# SCH_Macropad.net
KiCad netlist of a schematic drawn in EasyEDA
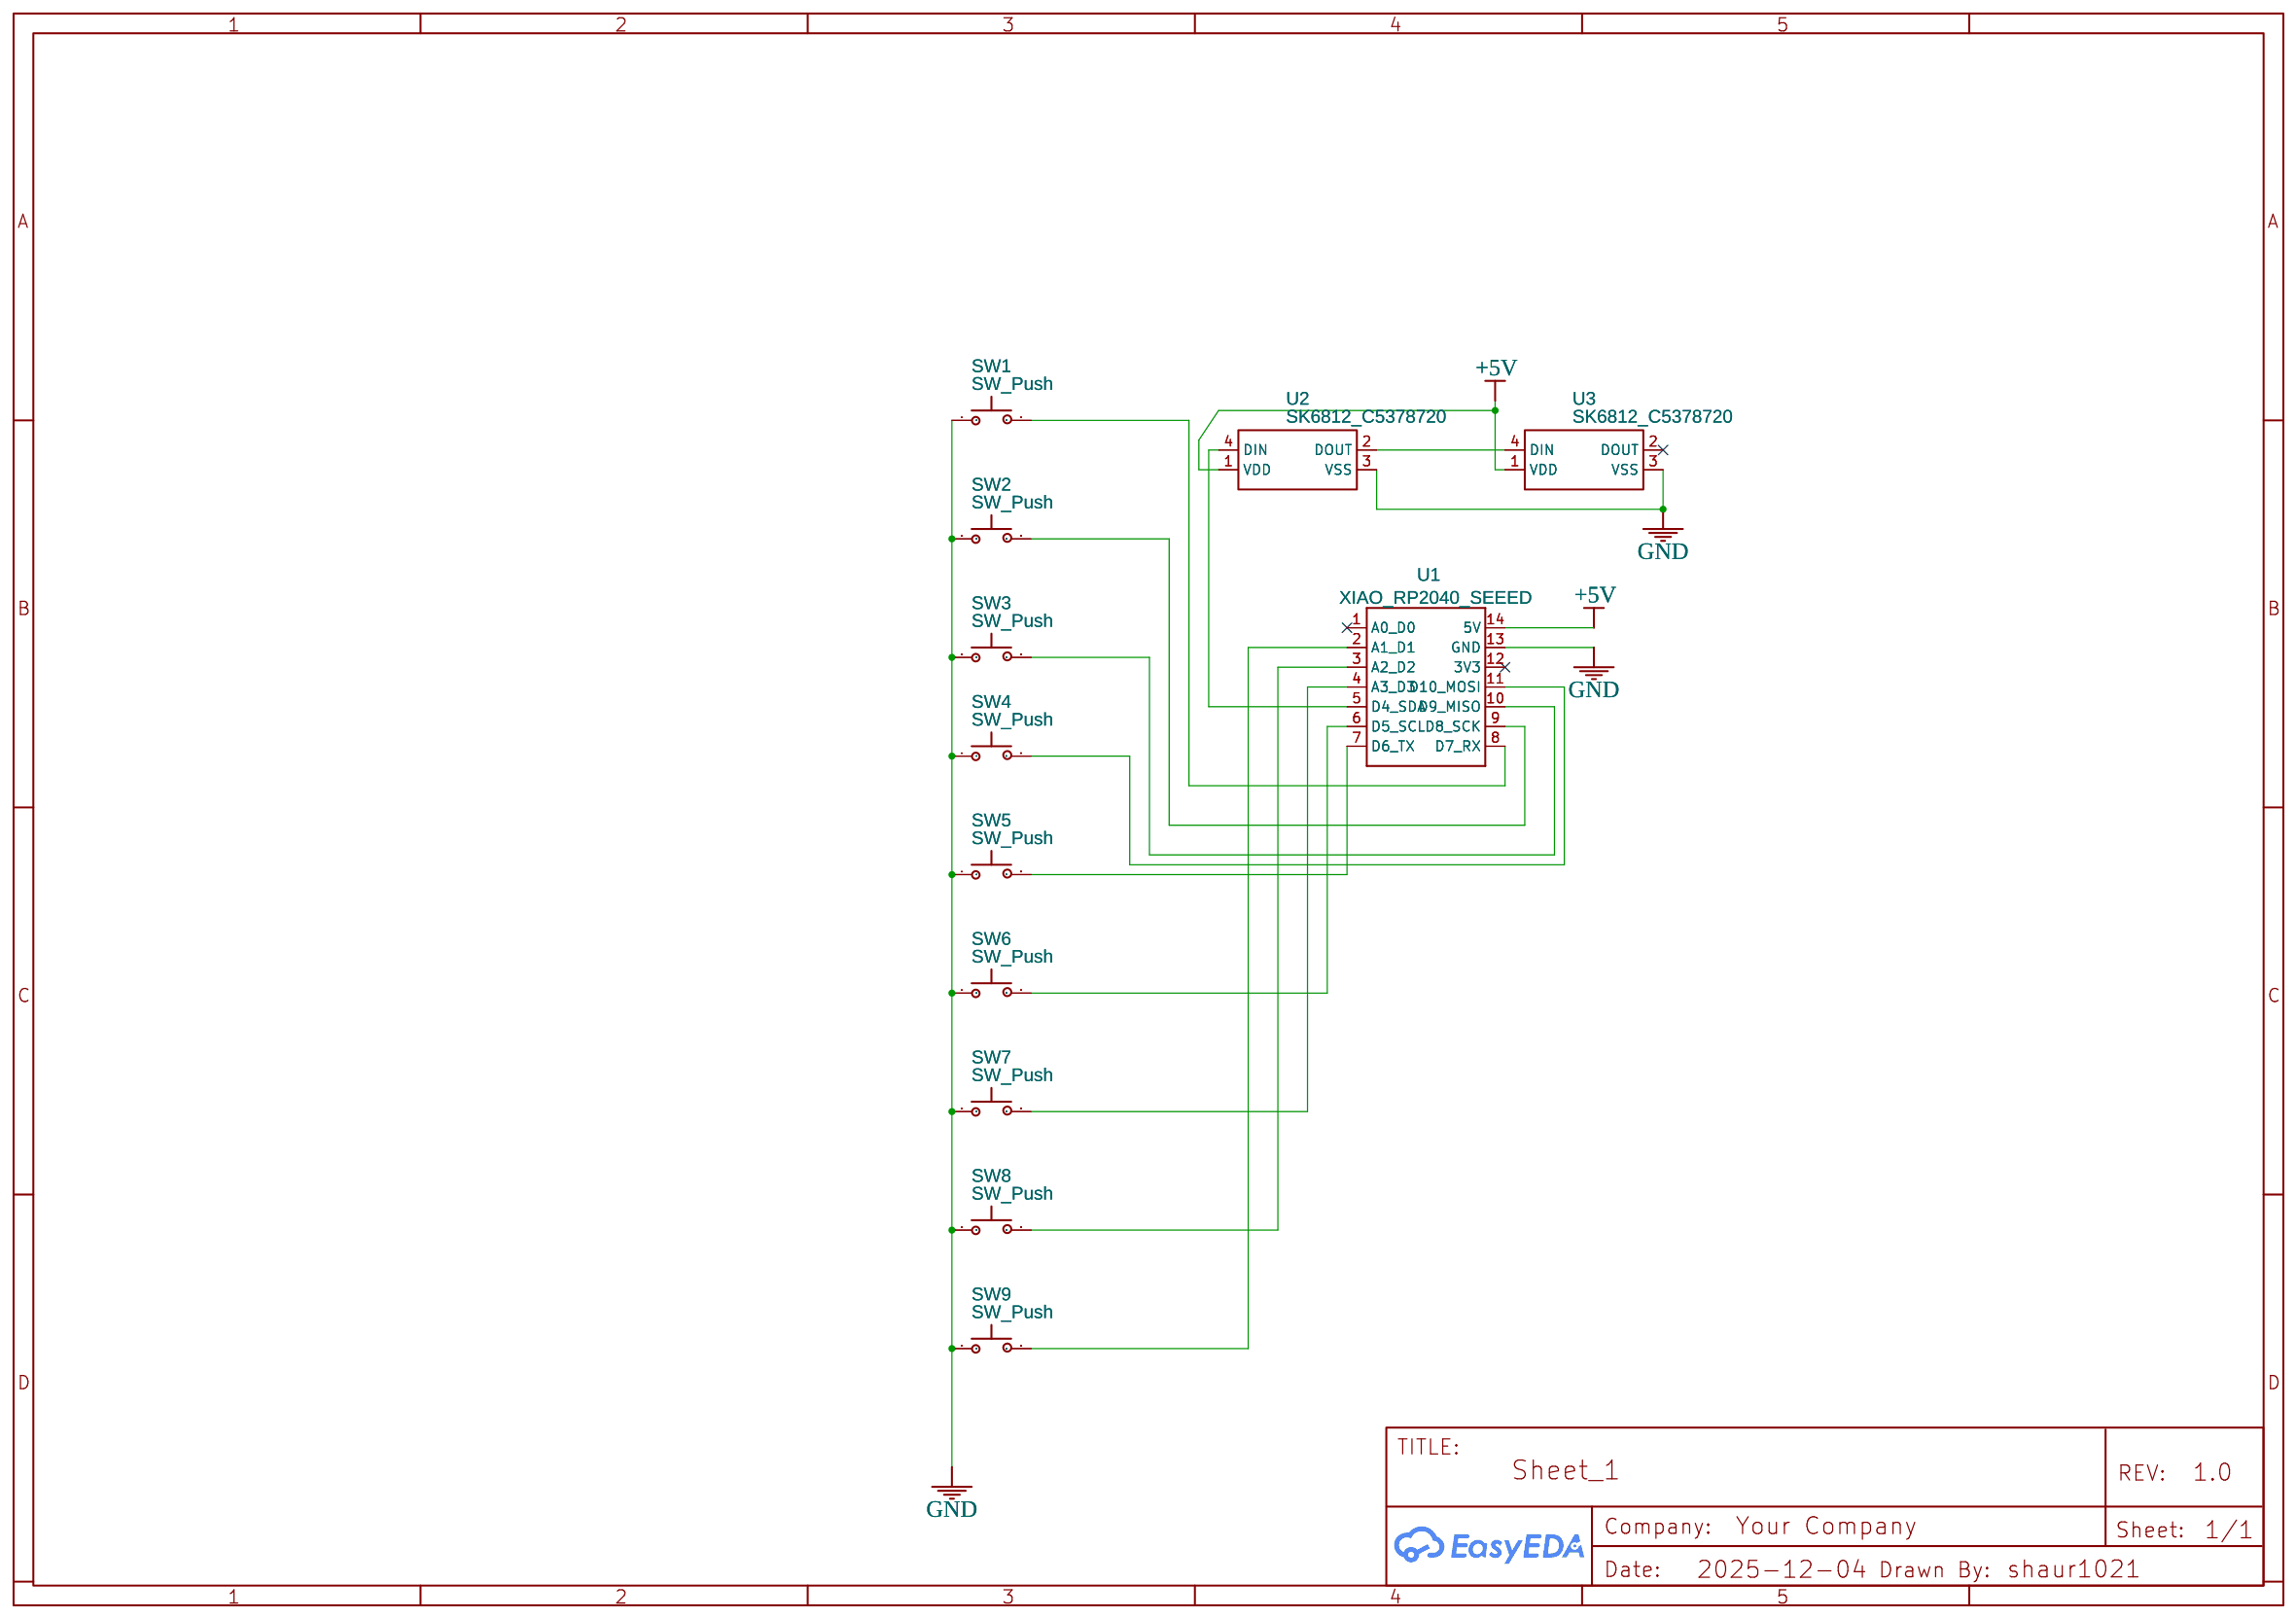
[diagram p0: schematic sheet]

(export (version "E")
  (design (tool "Eeschema 10.0.6"))
  (components
    (comp (ref "SW1") (value "SW_Push") (libsource (lib "") (part "SW_Push")))
    (comp (ref "SW2") (value "SW_Push") (libsource (lib "") (part "SW_Push")))
    (comp (ref "SW3") (value "SW_Push") (libsource (lib "") (part "SW_Push")))
    (comp (ref "SW4") (value "SW_Push") (libsource (lib "") (part "SW_Push")))
    (comp (ref "SW5") (value "SW_Push") (libsource (lib "") (part "SW_Push")))
    (comp (ref "SW6") (value "SW_Push") (libsource (lib "") (part "SW_Push")))
    (comp (ref "SW7") (value "SW_Push") (libsource (lib "") (part "SW_Push")))
    (comp (ref "SW8") (value "SW_Push") (libsource (lib "") (part "SW_Push")))
    (comp (ref "SW9") (value "SW_Push") (libsource (lib "") (part "SW_Push")))
    (comp (ref "U1") (value "XIAO_RP2040_SEEED") (libsource (lib "") (part "XIAO_RP2040_SEEED")))
    (comp (ref "U2")
      (value "SK6812_C5378720")
      (fields (field (name "Manufacturer Part") "SK6812") (field (name "Manufacturer") "欧思科光电"))
      (libsource (lib "") (part "SK6812_C5378720"))
    )
    (comp (ref "U3")
      (value "SK6812_C5378720")
      (fields (field (name "Manufacturer Part") "SK6812") (field (name "Manufacturer") "欧思科光电"))
      (libsource (lib "") (part "SK6812_C5378720"))
    )
  )
  (nets
    (net (code "1") (name "+5V") (class "Default")
      (node (ref "U1") (pin "14") (pinfunction "5V_14") (pintype "bidirectional"))
      (node (ref "U2") (pin "1") (pinfunction "VDD_1") (pintype "unspecified"))
      (node (ref "U3") (pin "1") (pinfunction "VDD_1") (pintype "unspecified"))
    )
    (net (code "2") (name "GND") (class "Default")
      (node (ref "SW1") (pin "1") (pinfunction "1_1") (pintype "unspecified"))
      (node (ref "SW2") (pin "1") (pinfunction "1_1") (pintype "unspecified"))
      (node (ref "SW3") (pin "1") (pinfunction "1_1") (pintype "unspecified"))
      (node (ref "SW4") (pin "1") (pinfunction "1_1") (pintype "unspecified"))
      (node (ref "SW5") (pin "1") (pinfunction "1_1") (pintype "unspecified"))
      (node (ref "SW6") (pin "1") (pinfunction "1_1") (pintype "unspecified"))
      (node (ref "SW7") (pin "1") (pinfunction "1_1") (pintype "unspecified"))
      (node (ref "SW8") (pin "1") (pinfunction "1_1") (pintype "unspecified"))
      (node (ref "SW9") (pin "1") (pinfunction "1_1") (pintype "unspecified"))
      (node (ref "U1") (pin "13") (pinfunction "GND_13") (pintype "bidirectional"))
      (node (ref "U2") (pin "3") (pinfunction "VSS_3") (pintype "unspecified"))
      (node (ref "U3") (pin "3") (pinfunction "VSS_3") (pintype "unspecified"))
    )
    (net (code "3") (name "Net-(U1-A1_D1)") (class "Default")
      (node (ref "SW9") (pin "2") (pinfunction "2_2") (pintype "unspecified"))
      (node (ref "U1") (pin "2") (pinfunction "A1_D1_2") (pintype "bidirectional"))
    )
    (net (code "4") (name "Net-(U1-A2_D2)") (class "Default")
      (node (ref "SW8") (pin "2") (pinfunction "2_2") (pintype "unspecified"))
      (node (ref "U1") (pin "3") (pinfunction "A2_D2_3") (pintype "bidirectional"))
    )
    (net (code "5") (name "Net-(U1-A3_D3)") (class "Default")
      (node (ref "SW7") (pin "2") (pinfunction "2_2") (pintype "unspecified"))
      (node (ref "U1") (pin "4") (pinfunction "A3_D3_4") (pintype "bidirectional"))
    )
    (net (code "6") (name "Net-(U1-D4_SDA)") (class "Default")
      (node (ref "U1") (pin "5") (pinfunction "D4_SDA_5") (pintype "bidirectional"))
      (node (ref "U2") (pin "4") (pinfunction "DIN_4") (pintype "unspecified"))
    )
    (net (code "7") (name "Net-(U1-D5_SCL)") (class "Default")
      (node (ref "SW6") (pin "2") (pinfunction "2_2") (pintype "unspecified"))
      (node (ref "U1") (pin "6") (pinfunction "D5_SCL_6") (pintype "bidirectional"))
    )
    (net (code "8") (name "Net-(U1-D6_TX)") (class "Default")
      (node (ref "SW5") (pin "2") (pinfunction "2_2") (pintype "unspecified"))
      (node (ref "U1") (pin "7") (pinfunction "D6_TX_7") (pintype "bidirectional"))
    )
    (net (code "9") (name "Net-(U1-D7_RX)") (class "Default")
      (node (ref "SW1") (pin "2") (pinfunction "2_2") (pintype "unspecified"))
      (node (ref "U1") (pin "8") (pinfunction "D7_RX_8") (pintype "bidirectional"))
    )
    (net (code "10") (name "Net-(U1-D8_SCK)") (class "Default")
      (node (ref "SW2") (pin "2") (pinfunction "2_2") (pintype "unspecified"))
      (node (ref "U1") (pin "9") (pinfunction "D8_SCK_9") (pintype "bidirectional"))
    )
    (net (code "11") (name "Net-(U1-D9_MISO)") (class "Default")
      (node (ref "SW3") (pin "2") (pinfunction "2_2") (pintype "unspecified"))
      (node (ref "U1") (pin "10") (pinfunction "D9_MISO_10") (pintype "bidirectional"))
    )
    (net (code "12") (name "Net-(U1-D10_MOSI)") (class "Default")
      (node (ref "SW4") (pin "2") (pinfunction "2_2") (pintype "unspecified"))
      (node (ref "U1") (pin "11") (pinfunction "D10_MOSI_11") (pintype "bidirectional"))
    )
    (net (code "13") (name "Net-(U2-DOUT)") (class "Default")
      (node (ref "U2") (pin "2") (pinfunction "DOUT_2") (pintype "unspecified"))
      (node (ref "U3") (pin "4") (pinfunction "DIN_4") (pintype "unspecified"))
    )
    (net (code "14") (name "unconnected-(U1-3V3-Pad12)") (class "Default")
      (node (ref "U1") (pin "12") (pinfunction "3V3_12") (pintype "bidirectional+no_connect"))
    )
    (net (code "15") (name "unconnected-(U1-A0_D0-Pad1)") (class "Default")
      (node (ref "U1") (pin "1") (pinfunction "A0_D0_1") (pintype "bidirectional+no_connect"))
    )
    (net (code "16") (name "unconnected-(U3-DOUT-Pad2)") (class "Default")
      (node (ref "U3") (pin "2") (pinfunction "DOUT_2") (pintype "unspecified+no_connect"))
    )
  )
)
